# MCU.net
KiCad netlist of a schematic drawn in Altium Designer
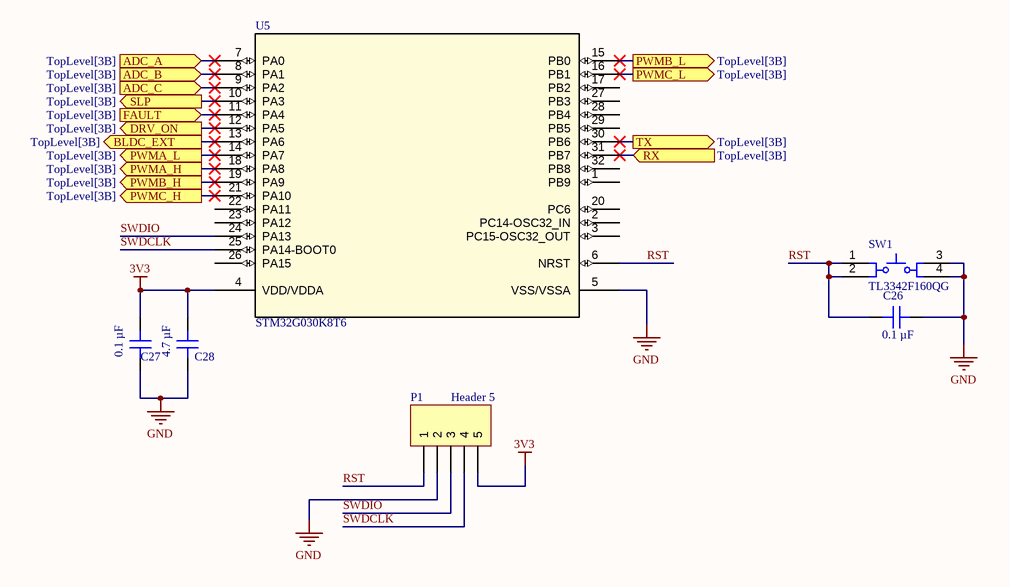
[diagram p0: MCU.SchDoc]

(export (version "E")
  (design (tool "Eeschema 10.0.6"))
  (components
    (comp (ref "C26")
      (value "0.1 µF")
      (footprint "CAP 0805_2012")
      (description "CAP CER 0.1UF 16V X7R 0805")
      (fields
        (field (name "PART NUMBER") "CC0805KRX7R7BB104")
        (field (name "CAPACITANCE") "0.1 µF")
        (field (name "MANUFACTURER") "Yageo")
      )
      (libsource (lib "Celestial Altium Library - altium_library") (part "Capacitor"))
    )
    (comp (ref "C27")
      (value "0.1 µF")
      (footprint "CAP 0805_2012")
      (description "CAP CER 0.1UF 16V X7R 0805")
      (fields
        (field (name "PART NUMBER") "CC0805KRX7R7BB104")
        (field (name "CAPACITANCE") "0.1 µF")
        (field (name "MANUFACTURER") "Yageo")
      )
      (libsource (lib "Celestial Altium Library - altium_library") (part "Capacitor"))
    )
    (comp (ref "C28")
      (value "4.7 µF")
      (footprint "CAP 0805_2012")
      (description "CAP CER 4.7UF 10V X5R 0805")
      (fields
        (field (name "PART NUMBER") "CC0805KRX5R6BB475")
        (field (name "CAPACITANCE") "4.7 µF")
        (field (name "MANUFACTURER") "Yageo")
      )
      (libsource (lib "Celestial Altium Library - altium_library") (part "Capacitor"))
    )
    (comp (ref "P1")
      (value "Header 5")
      (footprint "HDR1X5")
      (description "Header, 5-Pin")
      (fields (field (name "PUBLISHER") "Altium Limited"))
      (libsource (lib "Miscellaneous Connectors") (part "Header 5"))
    )
    (comp (ref "SW1")
      (value "TL3342F160QG")
      (footprint "ESWI-TL3342F160QG_V")
      (description "Switch, Tactile, SPST-NO, 50 mA, 12 V, 4-Pin SMD, RoHS, Tape and Reel")
      (fields (field (name "TOLERANCE") "20%"))
      (libsource (lib "TL3342F160QG") (part "TL3342F160QG"))
    )
    (comp (ref "U5")
      (value "STM32G030K8T6")
      (footprint "LQFP-32")
      (description "No Description Available")
      (libsource (lib "STM32G030K8T6") (part "STM32G030K8T6"))
    )
  )
  (nets
    (net (code "1") (name "/ADC_A") (class "Default")
      (node (ref "U5") (pin "7") (pinfunction "PA0_7") (pintype "bidirectional+no_connect"))
    )
    (net (code "2") (name "/ADC_B") (class "Default")
      (node (ref "U5") (pin "8") (pinfunction "PA1_8") (pintype "bidirectional+no_connect"))
    )
    (net (code "3") (name "/ADC_C") (class "Default")
      (node (ref "U5") (pin "9") (pinfunction "PA2_9") (pintype "bidirectional+no_connect"))
    )
    (net (code "4") (name "/BLDC_EXT") (class "Default")
      (node (ref "U5") (pin "13") (pinfunction "PA6_13") (pintype "bidirectional+no_connect"))
    )
    (net (code "5") (name "/DRV_ON") (class "Default")
      (node (ref "U5") (pin "12") (pinfunction "PA5_12") (pintype "bidirectional+no_connect"))
    )
    (net (code "6") (name "/FAULT") (class "Default")
      (node (ref "U5") (pin "11") (pinfunction "PA4_11") (pintype "bidirectional+no_connect"))
    )
    (net (code "7") (name "/PWMA_H") (class "Default")
      (node (ref "U5") (pin "18") (pinfunction "PA8_18") (pintype "bidirectional+no_connect"))
    )
    (net (code "8") (name "/PWMA_L") (class "Default")
      (node (ref "U5") (pin "14") (pinfunction "PA7_14") (pintype "bidirectional+no_connect"))
    )
    (net (code "9") (name "/PWMB_H") (class "Default")
      (node (ref "U5") (pin "19") (pinfunction "PA9_19") (pintype "bidirectional+no_connect"))
    )
    (net (code "10") (name "/PWMB_L") (class "Default")
      (node (ref "U5") (pin "15") (pinfunction "PB0_15") (pintype "bidirectional+no_connect"))
    )
    (net (code "11") (name "/PWMC_H") (class "Default")
      (node (ref "U5") (pin "21") (pinfunction "PA10_21") (pintype "bidirectional+no_connect"))
    )
    (net (code "12") (name "/PWMC_L") (class "Default")
      (node (ref "U5") (pin "16") (pinfunction "PB1_16") (pintype "bidirectional+no_connect"))
    )
    (net (code "13") (name "/RST") (class "Default")
      (node (ref "C26") (pin "2") (pinfunction "2_2") (pintype "passive"))
      (node (ref "P1") (pin "1") (pinfunction "1_1") (pintype "passive"))
      (node (ref "SW1") (pin "1") (pinfunction "1_1") (pintype "passive"))
      (node (ref "SW1") (pin "2") (pinfunction "2_2") (pintype "passive"))
      (node (ref "U5") (pin "6") (pinfunction "NRST_6") (pintype "bidirectional"))
    )
    (net (code "14") (name "/RX") (class "Default")
      (node (ref "U5") (pin "31") (pinfunction "PB7_31") (pintype "bidirectional+no_connect"))
    )
    (net (code "15") (name "/SLP") (class "Default")
      (node (ref "U5") (pin "10") (pinfunction "PA3_10") (pintype "bidirectional+no_connect"))
    )
    (net (code "16") (name "/SWDCLK") (class "Default")
      (node (ref "P1") (pin "4") (pinfunction "4_4") (pintype "passive"))
      (node (ref "U5") (pin "25") (pinfunction "PA14-BOOT0_25") (pintype "bidirectional"))
    )
    (net (code "17") (name "/SWDIO") (class "Default")
      (node (ref "P1") (pin "3") (pinfunction "3_3") (pintype "passive"))
      (node (ref "U5") (pin "24") (pinfunction "PA13_24") (pintype "bidirectional"))
    )
    (net (code "18") (name "/TX") (class "Default")
      (node (ref "U5") (pin "30") (pinfunction "PB6_30") (pintype "bidirectional+no_connect"))
    )
    (net (code "19") (name "3V3") (class "Default")
      (node (ref "C27") (pin "2") (pinfunction "2_2") (pintype "passive"))
      (node (ref "C28") (pin "2") (pinfunction "2_2") (pintype "passive"))
      (node (ref "P1") (pin "5") (pinfunction "5_5") (pintype "passive"))
      (node (ref "U5") (pin "4") (pinfunction "VDD/VDDA_4") (pintype "power_in"))
    )
    (net (code "20") (name "GND") (class "Default")
      (node (ref "C26") (pin "1") (pinfunction "1_1") (pintype "passive"))
      (node (ref "C27") (pin "1") (pinfunction "1_1") (pintype "passive"))
      (node (ref "C28") (pin "1") (pinfunction "1_1") (pintype "passive"))
      (node (ref "P1") (pin "2") (pinfunction "2_2") (pintype "passive"))
      (node (ref "SW1") (pin "3") (pinfunction "3_3") (pintype "passive"))
      (node (ref "SW1") (pin "4") (pinfunction "4_4") (pintype "passive"))
      (node (ref "U5") (pin "5") (pinfunction "VSS/VSSA_5") (pintype "power_in"))
    )
    (net (code "21") (name "unconnected-(U5-PA11-Pad22)") (class "Default")
      (node (ref "U5") (pin "22") (pinfunction "PA11_22") (pintype "bidirectional"))
    )
    (net (code "22") (name "unconnected-(U5-PA12-Pad23)") (class "Default")
      (node (ref "U5") (pin "23") (pinfunction "PA12_23") (pintype "bidirectional"))
    )
    (net (code "23") (name "unconnected-(U5-PA15-Pad26)") (class "Default")
      (node (ref "U5") (pin "26") (pinfunction "PA15_26") (pintype "bidirectional"))
    )
    (net (code "24") (name "unconnected-(U5-PB2-Pad17)") (class "Default")
      (node (ref "U5") (pin "17") (pinfunction "PB2_17") (pintype "bidirectional"))
    )
    (net (code "25") (name "unconnected-(U5-PB3-Pad27)") (class "Default")
      (node (ref "U5") (pin "27") (pinfunction "PB3_27") (pintype "bidirectional"))
    )
    (net (code "26") (name "unconnected-(U5-PB4-Pad28)") (class "Default")
      (node (ref "U5") (pin "28") (pinfunction "PB4_28") (pintype "bidirectional"))
    )
    (net (code "27") (name "unconnected-(U5-PB5-Pad29)") (class "Default")
      (node (ref "U5") (pin "29") (pinfunction "PB5_29") (pintype "bidirectional"))
    )
    (net (code "28") (name "unconnected-(U5-PB8-Pad32)") (class "Default")
      (node (ref "U5") (pin "32") (pinfunction "PB8_32") (pintype "bidirectional"))
    )
    (net (code "29") (name "unconnected-(U5-PB9-Pad1)") (class "Default")
      (node (ref "U5") (pin "1") (pinfunction "PB9_1") (pintype "bidirectional"))
    )
    (net (code "30") (name "unconnected-(U5-PC6-Pad20)") (class "Default")
      (node (ref "U5") (pin "20") (pinfunction "PC6_20") (pintype "bidirectional"))
    )
    (net (code "31") (name "unconnected-(U5-PC14-OSC32_IN-Pad2)") (class "Default")
      (node (ref "U5") (pin "2") (pinfunction "PC14-OSC32_IN_2") (pintype "bidirectional"))
    )
    (net (code "32") (name "unconnected-(U5-PC15-OSC32_OUT-Pad3)") (class "Default")
      (node (ref "U5") (pin "3") (pinfunction "PC15-OSC32_OUT_3") (pintype "bidirectional"))
    )
  )
)
